# LPCB220_-_G210X_MUX_INTERFACE.net
KiCad netlist of a schematic drawn in Altium Designer
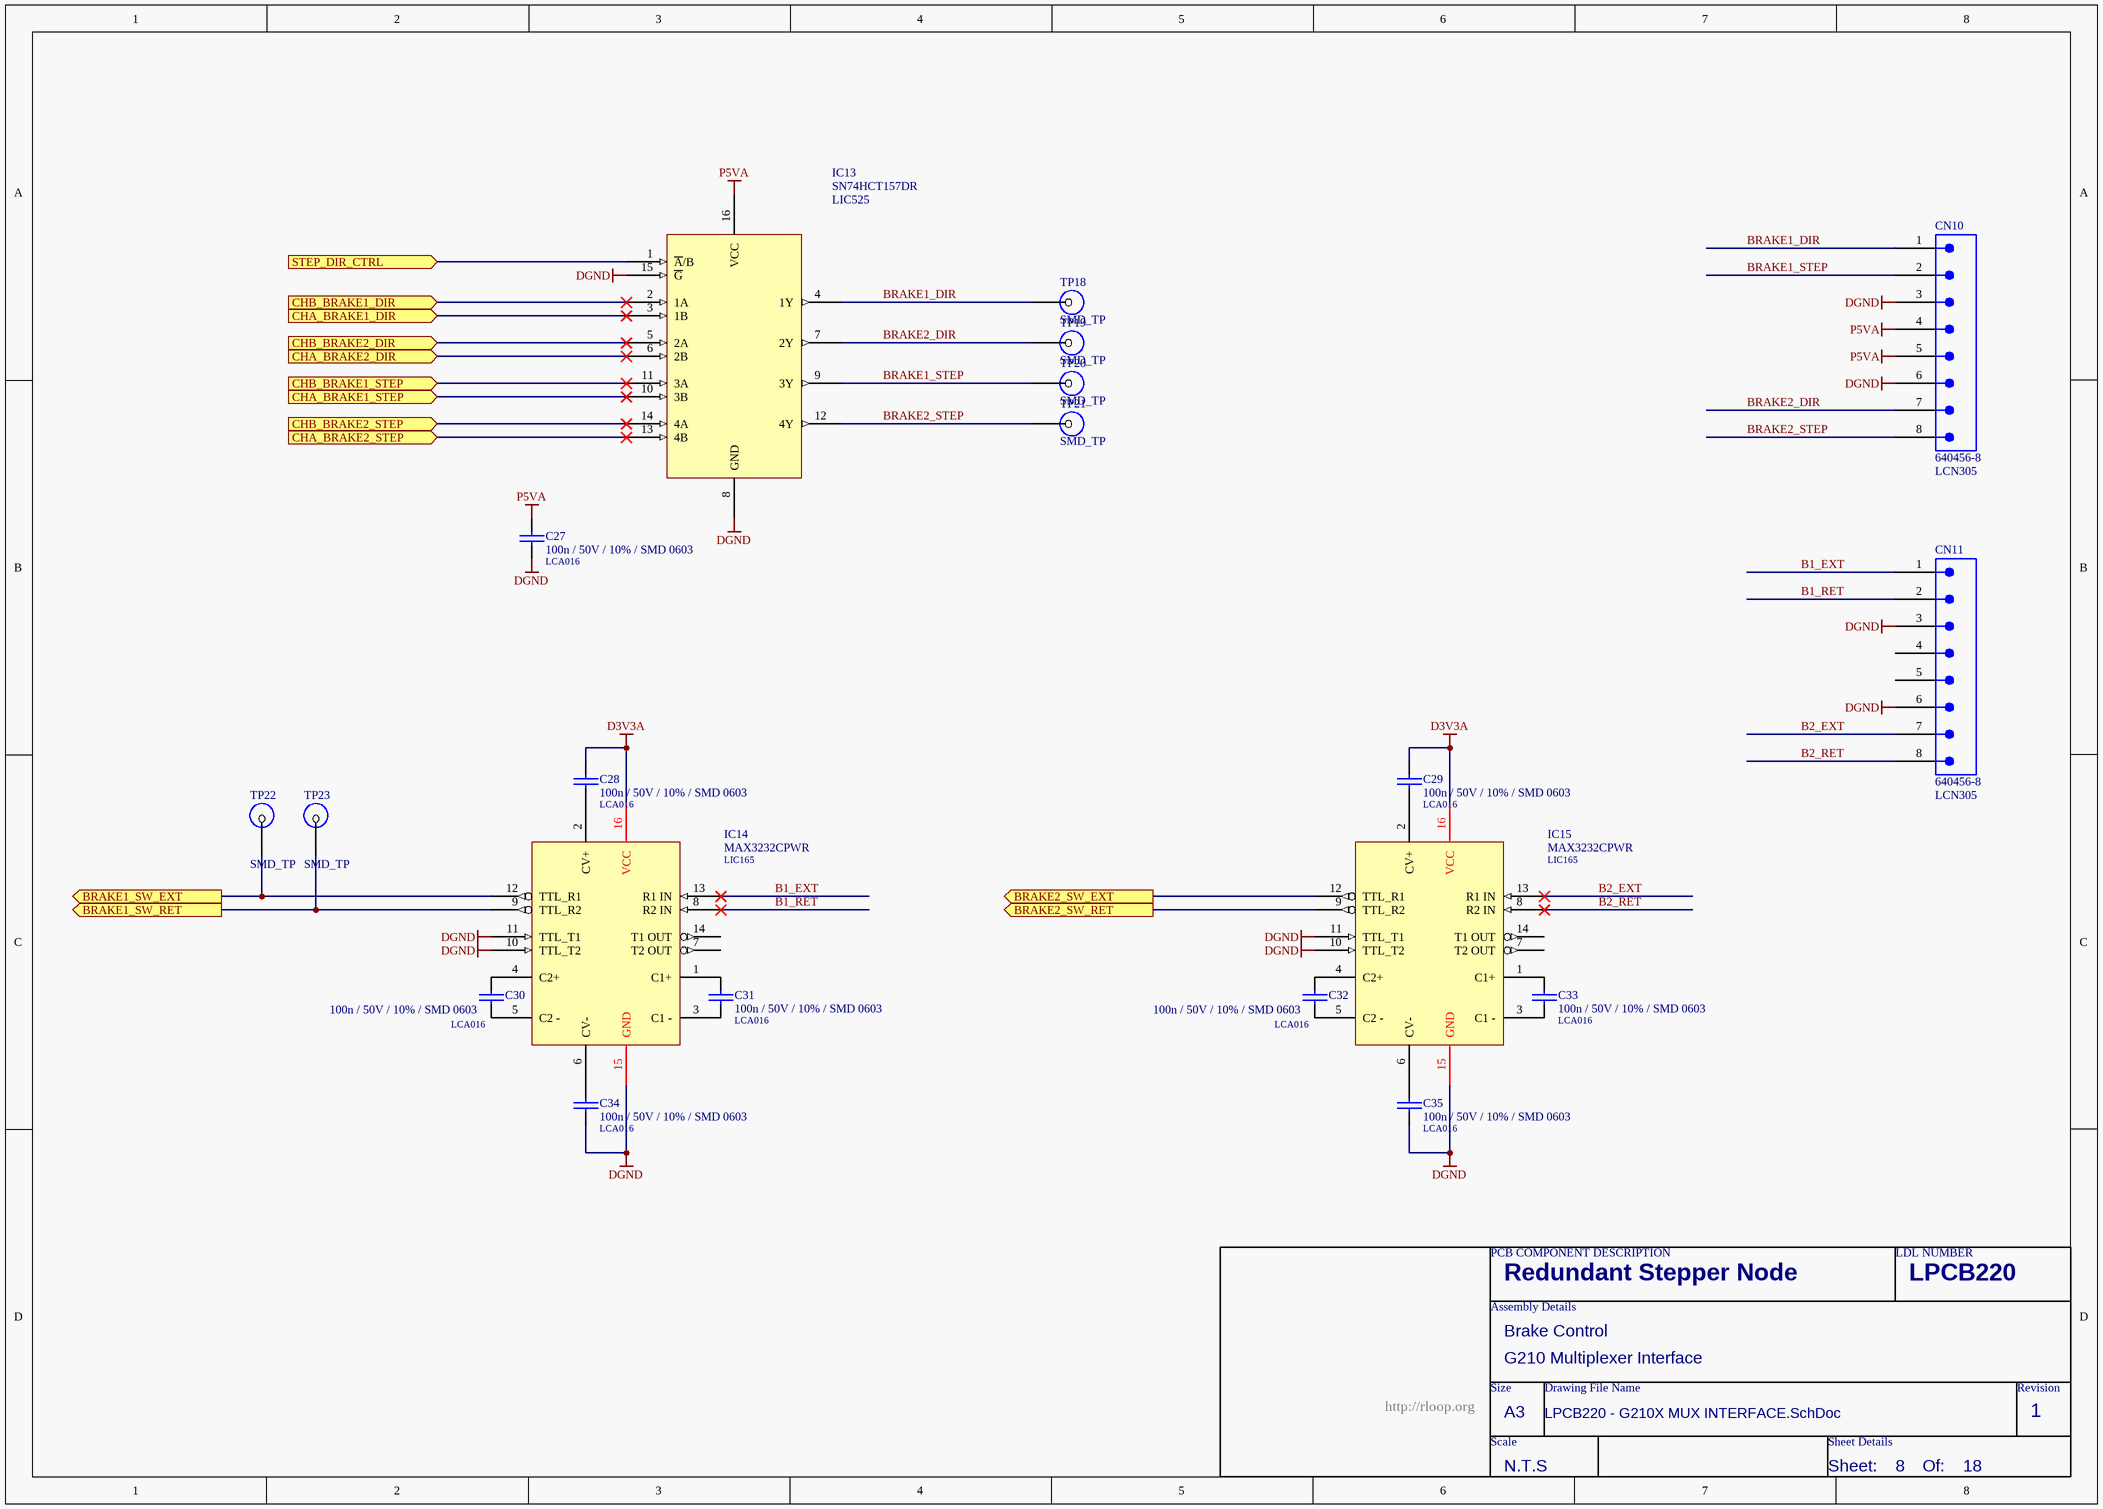
[diagram p0: LPCB220 - G210X MUX INTERFACE.SchDoc]

(export (version "E")
  (design (tool "Eeschema 10.0.6"))
  (components
    (comp (ref "C27")
      (value "100n / 50V / 10% / SMD 0603")
      (footprint "LFP011__CC1608-0603-IPC7351_B")
      (description "Capacitor, Ceramic Chip, 100nF (0.1uF), 50V, 5%, SMD 0603 [LCA016]")
      (fields (field (name "LDL_NUMBER") "LCA016"))
      (libsource (lib "LDL_Capacitors") (part "100n / 50V / 10% / SMD 0603"))
    )
    (comp (ref "C28")
      (value "100n / 50V / 10% / SMD 0603")
      (footprint "LFP011__CC1608-0603-IPC7351_B")
      (description "Capacitor, Ceramic Chip, 100nF, 50V, 10%, SMD 0603")
      (fields (field (name "LDL_NUMBER") "LCA016"))
      (libsource (lib "LDL_Capacitors") (part "100n / 50V / 10% / SMD 0603"))
    )
    (comp (ref "C29")
      (value "100n / 50V / 10% / SMD 0603")
      (footprint "LFP011__CC1608-0603-IPC7351_B")
      (description "Capacitor, Ceramic Chip, 100nF, 50V, 10%, SMD 0603")
      (fields (field (name "LDL_NUMBER") "LCA016"))
      (libsource (lib "LDL_Capacitors") (part "100n / 50V / 10% / SMD 0603"))
    )
    (comp (ref "C30")
      (value "100n / 50V / 10% / SMD 0603")
      (footprint "LFP011__CC1608-0603-IPC7351_B")
      (description "Capacitor, Ceramic Chip, 100nF, 50V, 10%, SMD 0603")
      (fields (field (name "LDL_NUMBER") "LCA016"))
      (libsource (lib "LDL_Capacitors") (part "100n / 50V / 10% / SMD 0603"))
    )
    (comp (ref "C31")
      (value "100n / 50V / 10% / SMD 0603")
      (footprint "LFP011__CC1608-0603-IPC7351_B")
      (description "Capacitor, Ceramic Chip, 100nF, 50V, 10%, SMD 0603")
      (fields (field (name "LDL_NUMBER") "LCA016"))
      (libsource (lib "LDL_Capacitors") (part "100n / 50V / 10% / SMD 0603"))
    )
    (comp (ref "C32")
      (value "100n / 50V / 10% / SMD 0603")
      (footprint "LFP011__CC1608-0603-IPC7351_B")
      (description "Capacitor, Ceramic Chip, 100nF, 50V, 10%, SMD 0603")
      (fields (field (name "LDL_NUMBER") "LCA016"))
      (libsource (lib "LDL_Capacitors") (part "100n / 50V / 10% / SMD 0603"))
    )
    (comp (ref "C33")
      (value "100n / 50V / 10% / SMD 0603")
      (footprint "LFP011__CC1608-0603-IPC7351_B")
      (description "Capacitor, Ceramic Chip, 100nF, 50V, 10%, SMD 0603")
      (fields (field (name "LDL_NUMBER") "LCA016"))
      (libsource (lib "LDL_Capacitors") (part "100n / 50V / 10% / SMD 0603"))
    )
    (comp (ref "C34")
      (value "100n / 50V / 10% / SMD 0603")
      (footprint "LFP011__CC1608-0603-IPC7351_B")
      (description "Capacitor, Ceramic Chip, 100nF, 50V, 10%, SMD 0603")
      (fields (field (name "LDL_NUMBER") "LCA016"))
      (libsource (lib "LDL_Capacitors") (part "100n / 50V / 10% / SMD 0603"))
    )
    (comp (ref "C35")
      (value "100n / 50V / 10% / SMD 0603")
      (footprint "LFP011__CC1608-0603-IPC7351_B")
      (description "Capacitor, Ceramic Chip, 100nF, 50V, 10%, SMD 0603")
      (fields (field (name "LDL_NUMBER") "LCA016"))
      (libsource (lib "LDL_Capacitors") (part "100n / 50V / 10% / SMD 0603"))
    )
    (comp (ref "CN10")
      (value "640456-8")
      (footprint "640456-8")
      (description "Connector, Male Header, 8 Way")
      (fields (field (name "LDL_NUMBER") "LCN305"))
      (libsource (lib "LDL_Connectors") (part "640456-8"))
    )
    (comp (ref "CN11")
      (value "640456-8")
      (footprint "640456-8")
      (description "Connector, Male Header, 8 Way")
      (fields (field (name "LDL_NUMBER") "LCN305"))
      (libsource (lib "LDL_Connectors") (part "640456-8"))
    )
    (comp (ref "IC13")
      (value "SN74HCT157DR")
      (footprint "LFP079__SOP16")
      (description "IC, Multiplexer Select 2-1 [LIC525]")
      (fields (field (name "LDL_NUMBER") "LIC525"))
      (libsource (lib "LDL_Semiconductors") (part "SN74HCT157DR"))
    )
    (comp (ref "IC14")
      (value "MAX3232CPWR")
      (footprint "LFP049__TSSOP-16")
      (description "IC, RS232 Line Driver, 3.3V, SMD TSSOP16")
      (fields (field (name "LDL_NUMBER") "LIC165"))
      (libsource (lib "LDL_Semiconductors") (part "MAX3232CPWR"))
    )
    (comp (ref "IC15")
      (value "MAX3232CPWR")
      (footprint "LFP049__TSSOP-16")
      (description "IC, RS232 Line Driver, 3.3V, SMD TSSOP16")
      (fields (field (name "LDL_NUMBER") "LIC165"))
      (libsource (lib "LDL_Semiconductors") (part "MAX3232CPWR"))
    )
    (comp (ref "TP18")
      (value "SMD_TP")
      (footprint "SMD-TP")
      (description "SMD Test Point")
      (libsource (lib "LDL_Connectors") (part "SMD_TP"))
    )
    (comp (ref "TP19")
      (value "SMD_TP")
      (footprint "SMD-TP")
      (description "SMD Test Point")
      (libsource (lib "LDL_Connectors") (part "SMD_TP"))
    )
    (comp (ref "TP20")
      (value "SMD_TP")
      (footprint "SMD-TP")
      (description "SMD Test Point")
      (libsource (lib "LDL_Connectors") (part "SMD_TP"))
    )
    (comp (ref "TP21")
      (value "SMD_TP")
      (footprint "SMD-TP")
      (description "SMD Test Point")
      (libsource (lib "LDL_Connectors") (part "SMD_TP"))
    )
    (comp (ref "TP22")
      (value "SMD_TP")
      (footprint "SMD-TP")
      (description "SMD Test Point")
      (libsource (lib "LDL_Connectors") (part "SMD_TP"))
    )
    (comp (ref "TP23")
      (value "SMD_TP")
      (footprint "SMD-TP")
      (description "SMD Test Point")
      (libsource (lib "LDL_Connectors") (part "SMD_TP"))
    )
  )
  (nets
    (net (code "1") (name "/B1_EXT") (class "Default")
      (node (ref "CN11") (pin "1") (pinfunction "1_1") (pintype "passive"))
      (node (ref "IC14") (pin "13") (pinfunction "R1_IN_13") (pintype "input"))
    )
    (net (code "2") (name "/B1_RET") (class "Default")
      (node (ref "CN11") (pin "2") (pinfunction "2_2") (pintype "passive"))
      (node (ref "IC14") (pin "8") (pinfunction "R2_IN_8") (pintype "input"))
    )
    (net (code "3") (name "/B2_EXT") (class "Default")
      (node (ref "CN11") (pin "7") (pinfunction "7_7") (pintype "passive"))
      (node (ref "IC15") (pin "13") (pinfunction "R1_IN_13") (pintype "input"))
    )
    (net (code "4") (name "/B2_RET") (class "Default")
      (node (ref "CN11") (pin "8") (pinfunction "8_8") (pintype "passive"))
      (node (ref "IC15") (pin "8") (pinfunction "R2_IN_8") (pintype "input"))
    )
    (net (code "5") (name "/BRAKE1_DIR") (class "Default")
      (node (ref "CN10") (pin "1") (pinfunction "1_1") (pintype "passive"))
      (node (ref "IC13") (pin "4") (pinfunction "1Y_4") (pintype "output"))
      (node (ref "TP18") (pin "1") (pintype "passive"))
    )
    (net (code "6") (name "/BRAKE1_STEP") (class "Default")
      (node (ref "CN10") (pin "2") (pinfunction "2_2") (pintype "passive"))
      (node (ref "IC13") (pin "9") (pinfunction "3Y_9") (pintype "output"))
      (node (ref "TP20") (pin "1") (pintype "passive"))
    )
    (net (code "7") (name "/BRAKE1_SW_EXT") (class "Default")
      (node (ref "IC14") (pin "12") (pinfunction "TTL_R1_12") (pintype "output"))
      (node (ref "TP22") (pin "1") (pintype "passive"))
    )
    (net (code "8") (name "/BRAKE1_SW_RET") (class "Default")
      (node (ref "IC14") (pin "9") (pinfunction "TTL_R2_9") (pintype "output"))
      (node (ref "TP23") (pin "1") (pintype "passive"))
    )
    (net (code "9") (name "/BRAKE2_DIR") (class "Default")
      (node (ref "CN10") (pin "7") (pinfunction "7_7") (pintype "passive"))
      (node (ref "IC13") (pin "7") (pinfunction "2Y_7") (pintype "output"))
      (node (ref "TP19") (pin "1") (pintype "passive"))
    )
    (net (code "10") (name "/BRAKE2_STEP") (class "Default")
      (node (ref "CN10") (pin "8") (pinfunction "8_8") (pintype "passive"))
      (node (ref "IC13") (pin "12") (pinfunction "4Y_12") (pintype "output"))
      (node (ref "TP21") (pin "1") (pintype "passive"))
    )
    (net (code "11") (name "/BRAKE2_SW_EXT") (class "Default")
      (node (ref "IC15") (pin "12") (pinfunction "TTL_R1_12") (pintype "output"))
    )
    (net (code "12") (name "/BRAKE2_SW_RET") (class "Default")
      (node (ref "IC15") (pin "9") (pinfunction "TTL_R2_9") (pintype "output"))
    )
    (net (code "13") (name "/CHA_BRAKE1_DIR") (class "Default")
      (node (ref "IC13") (pin "3") (pinfunction "1B_3") (pintype "input+no_connect"))
    )
    (net (code "14") (name "/CHA_BRAKE1_STEP") (class "Default")
      (node (ref "IC13") (pin "10") (pinfunction "3B_10") (pintype "input+no_connect"))
    )
    (net (code "15") (name "/CHA_BRAKE2_DIR") (class "Default")
      (node (ref "IC13") (pin "6") (pinfunction "2B_6") (pintype "input+no_connect"))
    )
    (net (code "16") (name "/CHA_BRAKE2_STEP") (class "Default")
      (node (ref "IC13") (pin "13") (pinfunction "4B_13") (pintype "input+no_connect"))
    )
    (net (code "17") (name "/CHB_BRAKE1_DIR") (class "Default")
      (node (ref "IC13") (pin "2") (pinfunction "1A_2") (pintype "input+no_connect"))
    )
    (net (code "18") (name "/CHB_BRAKE1_STEP") (class "Default")
      (node (ref "IC13") (pin "11") (pinfunction "3A_11") (pintype "input+no_connect"))
    )
    (net (code "19") (name "/CHB_BRAKE2_DIR") (class "Default")
      (node (ref "IC13") (pin "5") (pinfunction "2A_5") (pintype "input+no_connect"))
    )
    (net (code "20") (name "/CHB_BRAKE2_STEP") (class "Default")
      (node (ref "IC13") (pin "14") (pinfunction "4A_14") (pintype "input+no_connect"))
    )
    (net (code "21") (name "/STEP_DIR_CTRL") (class "Default")
      (node (ref "IC13") (pin "1") (pinfunction "~{A}/B_1") (pintype "input"))
    )
    (net (code "22") (name "D3V3A") (class "Default")
      (node (ref "C28") (pin "1") (pintype "passive"))
      (node (ref "C29") (pin "1") (pintype "passive"))
      (node (ref "IC14") (pin "16") (pinfunction "VCC_16") (pintype "power_in"))
      (node (ref "IC15") (pin "16") (pinfunction "VCC_16") (pintype "power_in"))
    )
    (net (code "23") (name "DGND") (class "Default")
      (node (ref "C27") (pin "2") (pintype "passive"))
      (node (ref "C34") (pin "2") (pintype "passive"))
      (node (ref "C35") (pin "2") (pintype "passive"))
      (node (ref "CN10") (pin "3") (pinfunction "3_3") (pintype "passive"))
      (node (ref "CN10") (pin "6") (pinfunction "6_6") (pintype "passive"))
      (node (ref "CN11") (pin "3") (pinfunction "3_3") (pintype "passive"))
      (node (ref "CN11") (pin "6") (pinfunction "6_6") (pintype "passive"))
      (node (ref "IC13") (pin "15") (pinfunction "~{G}_15") (pintype "input"))
      (node (ref "IC13") (pin "8") (pinfunction "GND_8") (pintype "power_in"))
      (node (ref "IC14") (pin "10") (pinfunction "TTL_T2_10") (pintype "input"))
      (node (ref "IC14") (pin "11") (pinfunction "TTL_T1_11") (pintype "input"))
      (node (ref "IC14") (pin "15") (pinfunction "GND_15") (pintype "power_in"))
      (node (ref "IC15") (pin "10") (pinfunction "TTL_T2_10") (pintype "input"))
      (node (ref "IC15") (pin "11") (pinfunction "TTL_T1_11") (pintype "input"))
      (node (ref "IC15") (pin "15") (pinfunction "GND_15") (pintype "power_in"))
    )
    (net (code "24") (name "Net-(IC14-C1+)") (class "Default")
      (node (ref "C31") (pin "1") (pintype "passive"))
      (node (ref "IC14") (pin "1") (pinfunction "C1+_1") (pintype "passive"))
    )
    (net (code "25") (name "Net-(IC14-C1_-)") (class "Default")
      (node (ref "C31") (pin "2") (pintype "passive"))
      (node (ref "IC14") (pin "3") (pinfunction "C1_-_3") (pintype "passive"))
    )
    (net (code "26") (name "Net-(IC14-C2+)") (class "Default")
      (node (ref "C30") (pin "1") (pintype "passive"))
      (node (ref "IC14") (pin "4") (pinfunction "C2+_4") (pintype "passive"))
    )
    (net (code "27") (name "Net-(IC14-C2_-)") (class "Default")
      (node (ref "C30") (pin "2") (pintype "passive"))
      (node (ref "IC14") (pin "5") (pinfunction "C2_-_5") (pintype "passive"))
    )
    (net (code "28") (name "Net-(IC14-CV+)") (class "Default")
      (node (ref "C28") (pin "2") (pintype "passive"))
      (node (ref "IC14") (pin "2") (pinfunction "CV+_2") (pintype "passive"))
    )
    (net (code "29") (name "Net-(IC14-CV-)") (class "Default")
      (node (ref "C34") (pin "1") (pintype "passive"))
      (node (ref "IC14") (pin "6") (pinfunction "CV-_6") (pintype "passive"))
    )
    (net (code "30") (name "Net-(IC15-C1+)") (class "Default")
      (node (ref "C33") (pin "1") (pintype "passive"))
      (node (ref "IC15") (pin "1") (pinfunction "C1+_1") (pintype "passive"))
    )
    (net (code "31") (name "Net-(IC15-C1_-)") (class "Default")
      (node (ref "C33") (pin "2") (pintype "passive"))
      (node (ref "IC15") (pin "3") (pinfunction "C1_-_3") (pintype "passive"))
    )
    (net (code "32") (name "Net-(IC15-C2+)") (class "Default")
      (node (ref "C32") (pin "1") (pintype "passive"))
      (node (ref "IC15") (pin "4") (pinfunction "C2+_4") (pintype "passive"))
    )
    (net (code "33") (name "Net-(IC15-C2_-)") (class "Default")
      (node (ref "C32") (pin "2") (pintype "passive"))
      (node (ref "IC15") (pin "5") (pinfunction "C2_-_5") (pintype "passive"))
    )
    (net (code "34") (name "Net-(IC15-CV+)") (class "Default")
      (node (ref "C29") (pin "2") (pintype "passive"))
      (node (ref "IC15") (pin "2") (pinfunction "CV+_2") (pintype "passive"))
    )
    (net (code "35") (name "Net-(IC15-CV-)") (class "Default")
      (node (ref "C35") (pin "1") (pintype "passive"))
      (node (ref "IC15") (pin "6") (pinfunction "CV-_6") (pintype "passive"))
    )
    (net (code "36") (name "P5VA") (class "Default")
      (node (ref "C27") (pin "1") (pintype "passive"))
      (node (ref "CN10") (pin "4") (pinfunction "4_4") (pintype "passive"))
      (node (ref "CN10") (pin "5") (pinfunction "5_5") (pintype "passive"))
      (node (ref "IC13") (pin "16") (pinfunction "VCC_16") (pintype "power_in"))
    )
    (net (code "37") (name "unconnected-(CN11-Pad4)") (class "Default")
      (node (ref "CN11") (pin "4") (pinfunction "4_4") (pintype "passive"))
    )
    (net (code "38") (name "unconnected-(CN11-Pad5)") (class "Default")
      (node (ref "CN11") (pin "5") (pinfunction "5_5") (pintype "passive"))
    )
    (net (code "39") (name "unconnected-(IC14-T1_OUT-Pad14)") (class "Default")
      (node (ref "IC14") (pin "14") (pinfunction "T1_OUT_14") (pintype "output"))
    )
    (net (code "40") (name "unconnected-(IC14-T2_OUT-Pad7)") (class "Default")
      (node (ref "IC14") (pin "7") (pinfunction "T2_OUT_7") (pintype "output"))
    )
    (net (code "41") (name "unconnected-(IC15-T1_OUT-Pad14)") (class "Default")
      (node (ref "IC15") (pin "14") (pinfunction "T1_OUT_14") (pintype "output"))
    )
    (net (code "42") (name "unconnected-(IC15-T2_OUT-Pad7)") (class "Default")
      (node (ref "IC15") (pin "7") (pinfunction "T2_OUT_7") (pintype "output"))
    )
  )
)
